# 01_-_rpiInterface.net
KiCad netlist of a schematic drawn in Altium Designer
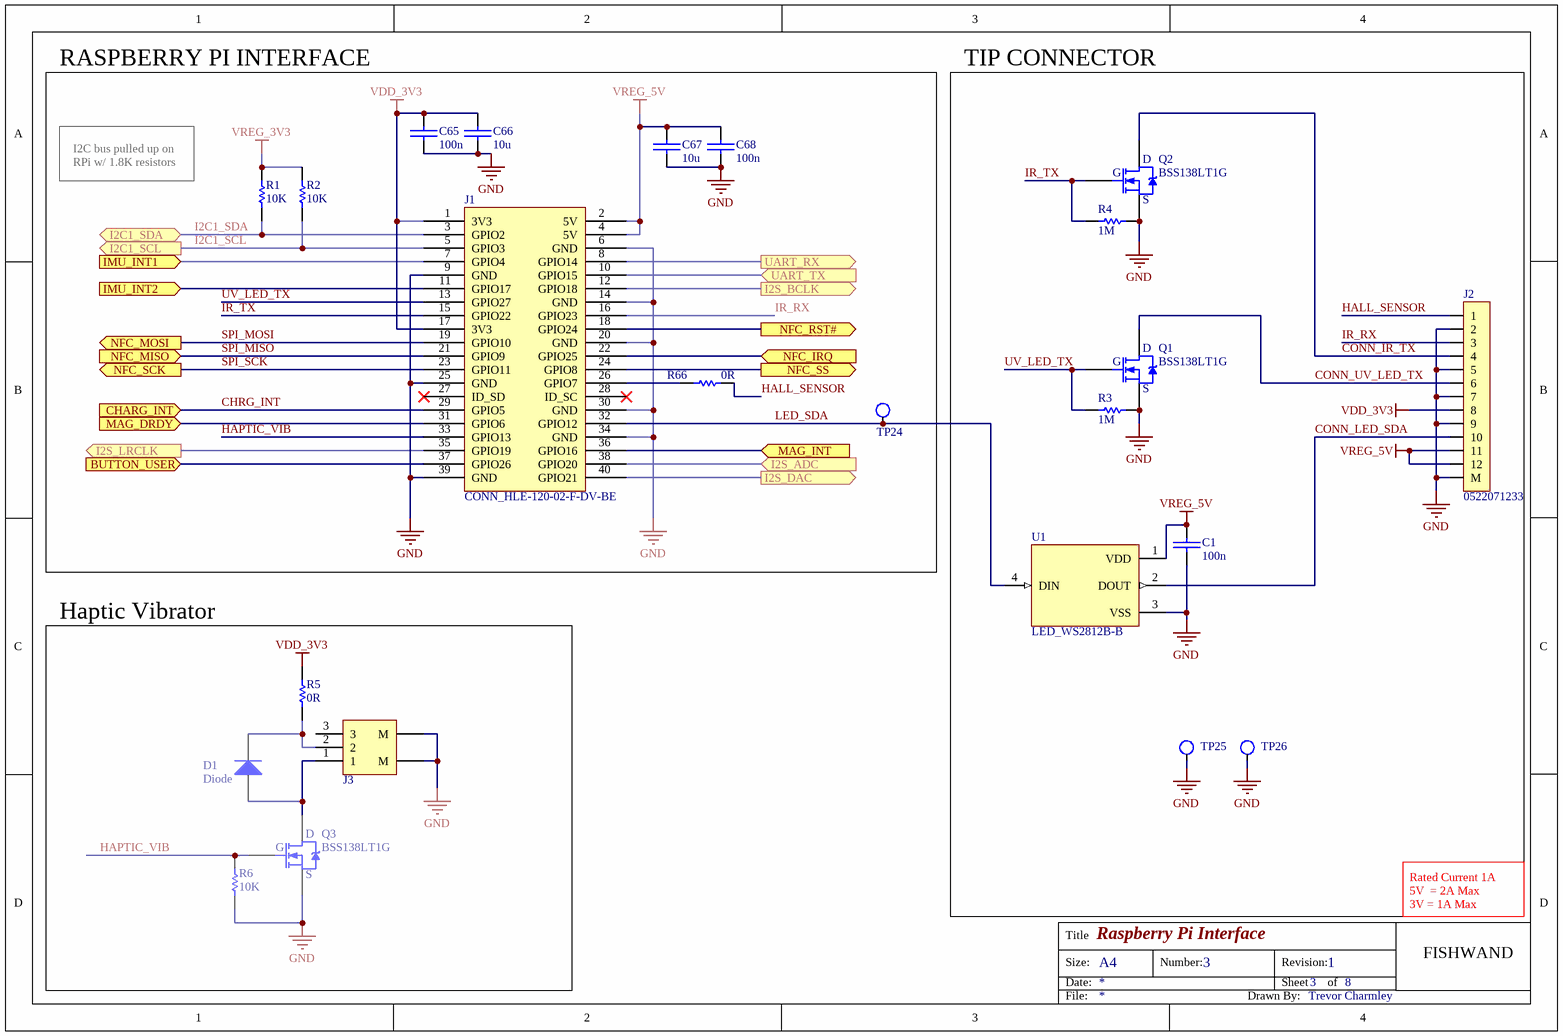
[diagram p0: 01 - rpiInterface.SchDoc]

(export (version "E")
  (design (tool "Eeschema 10.0.6"))
  (components
    (comp (ref "C1")
      (value "100n")
      (footprint "CAPC100X50X65")
      (description "CAP CER 100nF 25V X5R 0402")
      (fields (field (name "MANUFACTURER") "Murata Electronics"))
      (libsource (lib "FishWand_Schlib") (part "C_100NF_25V_X5R_0402"))
    )
    (comp (ref "C65")
      (value "100n")
      (footprint "CAPC100X50X65")
      (description "CAP CER 100nF 25V X5R 0402")
      (fields (field (name "MANUFACTURER") "Murata Electronics"))
      (libsource (lib "FishWand_Schlib") (part "C_100NF_25V_X5R_0402"))
    )
    (comp (ref "C66")
      (value "10u")
      (footprint "CAPC100X50X65")
      (description "CAP CER 10UF 10V X5R 0402")
      (fields (field (name "MANUFACTURER") "Samsung Electro-Mechanics"))
      (libsource (lib "FishWand_Schlib") (part "C_10UF_10V_X5R_0402"))
    )
    (comp (ref "C67")
      (value "10u")
      (footprint "CAPC100X50X65")
      (description "CAP CER 10UF 10V X5R 0402")
      (fields (field (name "MANUFACTURER") "Samsung Electro-Mechanics"))
      (libsource (lib "FishWand_Schlib") (part "C_10UF_10V_X5R_0402"))
    )
    (comp (ref "C68")
      (value "100n")
      (footprint "CAPC100X50X65")
      (description "CAP CER 100nF 25V X5R 0402")
      (fields (field (name "MANUFACTURER") "Murata Electronics"))
      (libsource (lib "FishWand_Schlib") (part "C_100NF_25V_X5R_0402"))
    )
    (comp (ref "D1")
      (value "Diode")
      (footprint "D_SOD_323F")
      (description "DIODE GEN PURP 75V 150MA SOD323F")
      (fields (field (name "MANUFACTURER") "onsemi"))
      (libsource (lib "FishWand_Schlib") (part "D_SOD_323_75V_150mA"))
    )
    (comp (ref "J1")
      (value "CONN_HLE-120-02-F-DV-BE")
      (footprint "FishWand_pcbLib:SAMTEC_HLE-120-02-F-DV-BE")
      (fields (field (name "MANUFACTURER") "Samtec"))
      (libsource (lib "FishWand_Schlib") (part "CONN_HLE-120-02-F-DV-BE"))
    )
    (comp (ref "J2")
      (value "0522071233")
      (footprint "CONN_0522711279")
      (description "CONN FPC BOTTOM 12POS 1.00MM R/A")
      (fields (field (name "MANUFACTURER") "Molex"))
      (libsource (lib "FishWand_Schlib") (part "CONN_FPC_Bottom 12POS_1MM_0522711279"))
    )
    (comp (ref "J3")
      (value "BM03B-ADHKS-GAN-ETB")
      (footprint "J_JST_BM03B-ADHKS-GAN-ETB")
      (description "CONN HEADER SMD R/A 3POS 1.3MM")
      (fields (field (name "MANUFACTURER") "JST Sales America Inc."))
      (libsource (lib "FishWand_Schlib") (part "CONN _HEADER SMD_3POS_1.3MM"))
    )
    (comp (ref "Q1")
      (value "BSS138LT1G")
      (footprint "SOT23-3P95_240X111L42X43N")
      (description "MOSFET N-CH 50V 200MA SOT-23")
      (fields (field (name "MANUFACTURER") "ON Semiconductor"))
      (libsource (lib "FishWand_Schlib") (part "TRANS_MOSFET_N_50V_200MA_SOT23"))
    )
    (comp (ref "Q2")
      (value "BSS138LT1G")
      (footprint "SOT23-3P95_240X111L42X43N")
      (description "MOSFET N-CH 50V 200MA SOT-23")
      (fields (field (name "MANUFACTURER") "ON Semiconductor"))
      (libsource (lib "FishWand_Schlib") (part "TRANS_MOSFET_N_50V_200MA_SOT23"))
    )
    (comp (ref "Q3")
      (value "BSS138LT1G")
      (footprint "SOT23-3P95_240X111L42X43N")
      (description "MOSFET N-CH 50V 200MA SOT-23")
      (fields (field (name "MANUFACTURER") "ON Semiconductor"))
      (libsource (lib "FishWand_Schlib") (part "TRANS_MOSFET_N_50V_200MA_SOT23"))
    )
    (comp (ref "R1")
      (value "10K")
      (footprint "RESC0402")
      (description "10 kOhms ±1% 0.063W, 1/16W Chip Resistor 0402 (1005 Metric) Moisture Resistant Thick Film")
      (fields (field (name "MANUFACTURER") "YAGEO") (field (name "TOLERANCE") "1%"))
      (libsource (lib "FishWand_Schlib") (part "R_0402_10K_1%"))
    )
    (comp (ref "R2")
      (value "10K")
      (footprint "RESC0402")
      (description "10 kOhms ±1% 0.063W, 1/16W Chip Resistor 0402 (1005 Metric) Moisture Resistant Thick Film")
      (fields (field (name "MANUFACTURER") "YAGEO") (field (name "TOLERANCE") "1%"))
      (libsource (lib "FishWand_Schlib") (part "R_0402_10K_1%"))
    )
    (comp (ref "R3")
      (value "1M")
      (footprint "RESC0402")
      (description "1 MOhms ±1% 0.063W, 1/16W Chip Resistor 0402 (1005 Metric) Moisture Resistant Thick Film")
      (fields (field (name "MANUFACTURER") "YAGEO") (field (name "TOLERANCE") "1%"))
      (libsource (lib "FishWand_Schlib") (part "R_0402_1M_1%"))
    )
    (comp (ref "R4")
      (value "1M")
      (footprint "RESC0402")
      (description "1 MOhms ±1% 0.063W, 1/16W Chip Resistor 0402 (1005 Metric) Moisture Resistant Thick Film")
      (fields (field (name "MANUFACTURER") "YAGEO") (field (name "TOLERANCE") "1%"))
      (libsource (lib "FishWand_Schlib") (part "R_0402_1M_1%"))
    )
    (comp (ref "R5")
      (value "0R")
      (footprint "RESC0402")
      (description "0 Ohms Jumper 0.063W, 1/16W Chip Resistor 0402 (1005 Metric) Thick Film")
      (fields (field (name "MANUFACTURER") "YAGEO") (field (name "TOLERANCE") "5%"))
      (libsource (lib "FishWand_Schlib") (part "R_0402_0R_5%"))
    )
    (comp (ref "R6")
      (value "10K")
      (footprint "RESC0402")
      (description "10 kOhms ±1% 0.063W, 1/16W Chip Resistor 0402 (1005 Metric) Moisture Resistant Thick Film")
      (fields (field (name "MANUFACTURER") "YAGEO") (field (name "TOLERANCE") "1%"))
      (libsource (lib "FishWand_Schlib") (part "R_0402_10K_1%"))
    )
    (comp (ref "R66")
      (value "0R")
      (footprint "RESC0402")
      (description "0 Ohms Jumper 0.063W, 1/16W Chip Resistor 0402 (1005 Metric) Thick Film")
      (fields (field (name "MANUFACTURER") "YAGEO") (field (name "TOLERANCE") "5%"))
      (libsource (lib "FishWand_Schlib") (part "R_0402_0R_5%"))
    )
    (comp (ref "TP24")
      (value "Test Point")
      (footprint "tp_1mm")
      (libsource (lib "FishWand_Schlib") (part "TP_1mm"))
    )
    (comp (ref "TP25")
      (value "Test Point")
      (footprint "tp_1mm")
      (libsource (lib "FishWand_Schlib") (part "TP_1mm"))
    )
    (comp (ref "TP26")
      (value "Test Point")
      (footprint "tp_1mm")
      (libsource (lib "FishWand_Schlib") (part "TP_1mm"))
    )
    (comp (ref "U1")
      (value "LED_WS2812B-B")
      (footprint "LED_WS2812B-B")
      (description "Intelligent control LED integrated light source")
      (fields (field (name "MANUFACTURER") "Worldsemi"))
      (libsource (lib "FishWand_Schlib") (part "LED_WS2812B-B"))
    )
  )
  (nets
    (net (code "1") (name "/BUTTON_USER") (class "Default")
      (node (ref "J1") (pin "37") (pinfunction "GPIO26_37") (pintype "passive"))
    )
    (net (code "2") (name "/CHRG_INT") (class "Default")
      (node (ref "J1") (pin "29") (pinfunction "GPIO5_29") (pintype "passive"))
    )
    (net (code "3") (name "/CONN_IR_TX") (class "Default")
      (node (ref "J2") (pin "4") (pinfunction "4_4") (pintype "passive"))
      (node (ref "Q2") (pin "3") (pinfunction "D_3") (pintype "passive"))
    )
    (net (code "4") (name "/CONN_LED_SDA") (class "Default")
      (node (ref "J2") (pin "10") (pinfunction "10_10") (pintype "passive"))
      (node (ref "U1") (pin "2") (pinfunction "DOUT_2") (pintype "output"))
    )
    (net (code "5") (name "/CONN_UV_LED_TX") (class "Default")
      (node (ref "J2") (pin "6") (pinfunction "6_6") (pintype "passive"))
      (node (ref "Q1") (pin "3") (pinfunction "D_3") (pintype "passive"))
    )
    (net (code "6") (name "/HALL_SENSOR") (class "Default")
      (node (ref "J2") (pin "1") (pinfunction "1_1") (pintype "passive"))
      (node (ref "R66") (pin "2") (pinfunction "2_2") (pintype "passive"))
    )
    (net (code "7") (name "/HAPTIC_VIB") (class "Default")
      (node (ref "J1") (pin "33") (pinfunction "GPIO13_33") (pintype "passive"))
      (node (ref "Q3") (pin "1") (pinfunction "G_1") (pintype "passive"))
      (node (ref "R6") (pin "2") (pinfunction "2_2") (pintype "passive"))
    )
    (net (code "8") (name "/I2C1_SCL") (class "Default")
      (node (ref "J1") (pin "5") (pinfunction "GPIO3_5") (pintype "passive"))
      (node (ref "R2") (pin "1") (pinfunction "1_1") (pintype "passive"))
    )
    (net (code "9") (name "/I2C1_SDA") (class "Default")
      (node (ref "J1") (pin "3") (pinfunction "GPIO2_3") (pintype "passive"))
      (node (ref "R1") (pin "1") (pinfunction "1_1") (pintype "passive"))
    )
    (net (code "10") (name "/I2S_ADC") (class "Default")
      (node (ref "J1") (pin "38") (pinfunction "GPIO20_38") (pintype "passive"))
    )
    (net (code "11") (name "/I2S_BCLK") (class "Default")
      (node (ref "J1") (pin "12") (pinfunction "GPIO18_12") (pintype "passive"))
    )
    (net (code "12") (name "/I2S_DAC") (class "Default")
      (node (ref "J1") (pin "40") (pinfunction "GPIO21_40") (pintype "passive"))
    )
    (net (code "13") (name "/I2S_LRCLK") (class "Default")
      (node (ref "J1") (pin "35") (pinfunction "GPIO19_35") (pintype "passive"))
    )
    (net (code "14") (name "/IMU_INT1") (class "Default")
      (node (ref "J1") (pin "7") (pinfunction "GPIO4_7") (pintype "passive"))
    )
    (net (code "15") (name "/IMU_INT2") (class "Default")
      (node (ref "J1") (pin "11") (pinfunction "GPIO17_11") (pintype "passive"))
    )
    (net (code "16") (name "/IR_RX") (class "Default")
      (node (ref "J1") (pin "16") (pinfunction "GPIO23_16") (pintype "passive"))
      (node (ref "J2") (pin "3") (pinfunction "3_3") (pintype "passive"))
    )
    (net (code "17") (name "/IR_TX") (class "Default")
      (node (ref "J1") (pin "15") (pinfunction "GPIO22_15") (pintype "passive"))
      (node (ref "Q2") (pin "1") (pinfunction "G_1") (pintype "passive"))
      (node (ref "R4") (pin "2") (pinfunction "2_2") (pintype "passive"))
    )
    (net (code "18") (name "/LED_SDA") (class "Default")
      (node (ref "J1") (pin "32") (pinfunction "GPIO12_32") (pintype "passive"))
      (node (ref "TP24") (pin "1") (pinfunction "1_1") (pintype "passive"))
      (node (ref "U1") (pin "4") (pinfunction "DIN_4") (pintype "input"))
    )
    (net (code "19") (name "/MAG_DRDY") (class "Default")
      (node (ref "J1") (pin "31") (pinfunction "GPIO6_31") (pintype "passive"))
    )
    (net (code "20") (name "/MAG_INT") (class "Default")
      (node (ref "J1") (pin "36") (pinfunction "GPIO16_36") (pintype "passive"))
    )
    (net (code "21") (name "/NFC_IRQ") (class "Default")
      (node (ref "J1") (pin "22") (pinfunction "GPIO25_22") (pintype "passive"))
    )
    (net (code "22") (name "/NFC_RST#") (class "Default")
      (node (ref "J1") (pin "18") (pinfunction "GPIO24_18") (pintype "passive"))
    )
    (net (code "23") (name "/NFC_SS") (class "Default")
      (node (ref "J1") (pin "24") (pinfunction "GPIO8_24") (pintype "passive"))
    )
    (net (code "24") (name "/SPI_MISO") (class "Default")
      (node (ref "J1") (pin "21") (pinfunction "GPIO9_21") (pintype "passive"))
    )
    (net (code "25") (name "/SPI_MOSI") (class "Default")
      (node (ref "J1") (pin "19") (pinfunction "GPIO10_19") (pintype "passive"))
    )
    (net (code "26") (name "/SPI_SCK") (class "Default")
      (node (ref "J1") (pin "23") (pinfunction "GPIO11_23") (pintype "passive"))
    )
    (net (code "27") (name "/UART_RX") (class "Default")
      (node (ref "J1") (pin "8") (pinfunction "GPIO14_8") (pintype "passive"))
    )
    (net (code "28") (name "/UART_TX") (class "Default")
      (node (ref "J1") (pin "10") (pinfunction "GPIO15_10") (pintype "passive"))
    )
    (net (code "29") (name "/UV_LED_TX") (class "Default")
      (node (ref "J1") (pin "13") (pinfunction "GPIO27_13") (pintype "passive"))
      (node (ref "Q1") (pin "1") (pinfunction "G_1") (pintype "passive"))
      (node (ref "R3") (pin "2") (pinfunction "2_2") (pintype "passive"))
    )
    (net (code "30") (name "GND") (class "Default")
      (node (ref "C1") (pin "2") (pinfunction "2_2") (pintype "passive"))
      (node (ref "C65") (pin "2") (pinfunction "2_2") (pintype "passive"))
      (node (ref "C66") (pin "2") (pinfunction "2_2") (pintype "passive"))
      (node (ref "C67") (pin "2") (pinfunction "2_2") (pintype "passive"))
      (node (ref "C68") (pin "2") (pinfunction "2_2") (pintype "passive"))
      (node (ref "J1") (pin "14") (pinfunction "GND_14") (pintype "power_in"))
      (node (ref "J1") (pin "20") (pinfunction "GND_20") (pintype "power_in"))
      (node (ref "J1") (pin "25") (pinfunction "GND_25") (pintype "power_in"))
      (node (ref "J1") (pin "30") (pinfunction "GND_30") (pintype "power_in"))
      (node (ref "J1") (pin "34") (pinfunction "GND_34") (pintype "power_in"))
      (node (ref "J1") (pin "39") (pinfunction "GND_39") (pintype "power_in"))
      (node (ref "J1") (pin "6") (pinfunction "GND_6") (pintype "power_in"))
      (node (ref "J1") (pin "9") (pinfunction "GND_9") (pintype "power_in"))
      (node (ref "J2") (pin "2") (pinfunction "2_2") (pintype "passive"))
      (node (ref "J2") (pin "5") (pinfunction "5_5") (pintype "passive"))
      (node (ref "J2") (pin "7") (pinfunction "7_7") (pintype "passive"))
      (node (ref "J2") (pin "9") (pinfunction "9_9") (pintype "passive"))
      (node (ref "J2") (pin "M") (pinfunction "M_M") (pintype "passive"))
      (node (ref "J3") (pin "0") (pinfunction "M_0") (pintype "passive"))
      (node (ref "Q1") (pin "2") (pinfunction "S_2") (pintype "passive"))
      (node (ref "Q2") (pin "2") (pinfunction "S_2") (pintype "passive"))
      (node (ref "Q3") (pin "2") (pinfunction "S_2") (pintype "passive"))
      (node (ref "R3") (pin "1") (pinfunction "1_1") (pintype "passive"))
      (node (ref "R4") (pin "1") (pinfunction "1_1") (pintype "passive"))
      (node (ref "R6") (pin "1") (pinfunction "1_1") (pintype "passive"))
      (node (ref "TP25") (pin "1") (pinfunction "1_1") (pintype "passive"))
      (node (ref "TP26") (pin "1") (pinfunction "1_1") (pintype "passive"))
      (node (ref "U1") (pin "3") (pinfunction "VSS_3") (pintype "power_in"))
    )
    (net (code "31") (name "Net-(D1-A)") (class "Default")
      (node (ref "D1") (pin "2") (pinfunction "A_2") (pintype "passive"))
      (node (ref "J3") (pin "1") (pinfunction "1_1") (pintype "passive"))
      (node (ref "Q3") (pin "3") (pinfunction "D_3") (pintype "passive"))
    )
    (net (code "32") (name "Net-(D1-K)") (class "Default")
      (node (ref "D1") (pin "1") (pinfunction "K_1") (pintype "passive"))
      (node (ref "J3") (pin "2") (pinfunction "2_2") (pintype "passive"))
      (node (ref "R5") (pin "1") (pinfunction "1_1") (pintype "passive"))
    )
    (net (code "33") (name "Net-(J1-GPIO7)") (class "Default")
      (node (ref "J1") (pin "26") (pinfunction "GPIO7_26") (pintype "passive"))
      (node (ref "R66") (pin "1") (pinfunction "1_1") (pintype "passive"))
    )
    (net (code "34") (name "VDD_3V3") (class "Default")
      (node (ref "C65") (pin "1") (pinfunction "1_1") (pintype "passive"))
      (node (ref "C66") (pin "1") (pinfunction "1_1") (pintype "passive"))
      (node (ref "J1") (pin "1") (pinfunction "3V3_1") (pintype "power_in"))
      (node (ref "J1") (pin "17") (pinfunction "3V3_17") (pintype "power_in"))
      (node (ref "J2") (pin "8") (pinfunction "8_8") (pintype "passive"))
      (node (ref "R5") (pin "2") (pinfunction "2_2") (pintype "passive"))
    )
    (net (code "35") (name "VREG_3V3") (class "Default")
      (node (ref "R1") (pin "2") (pinfunction "2_2") (pintype "passive"))
      (node (ref "R2") (pin "2") (pinfunction "2_2") (pintype "passive"))
    )
    (net (code "36") (name "VREG_5V") (class "Default")
      (node (ref "C1") (pin "1") (pinfunction "1_1") (pintype "passive"))
      (node (ref "C67") (pin "1") (pinfunction "1_1") (pintype "passive"))
      (node (ref "C68") (pin "1") (pinfunction "1_1") (pintype "passive"))
      (node (ref "J1") (pin "2") (pinfunction "5V_2") (pintype "power_in"))
      (node (ref "J1") (pin "4") (pinfunction "5V_4") (pintype "power_in"))
      (node (ref "J2") (pin "11") (pinfunction "11_11") (pintype "passive"))
      (node (ref "J2") (pin "12") (pinfunction "12_12") (pintype "passive"))
      (node (ref "U1") (pin "1") (pinfunction "VDD_1") (pintype "power_in"))
    )
    (net (code "37") (name "unconnected-(J1-ID_SC-Pad28)") (class "Default")
      (node (ref "J1") (pin "28") (pinfunction "ID_SC_28") (pintype "passive+no_connect"))
    )
    (net (code "38") (name "unconnected-(J1-ID_SD-Pad27)") (class "Default")
      (node (ref "J1") (pin "27") (pinfunction "ID_SD_27") (pintype "passive+no_connect"))
    )
    (net (code "39") (name "unconnected-(J3-Pad3)") (class "Default")
      (node (ref "J3") (pin "3") (pinfunction "3_3") (pintype "passive"))
    )
  )
)
